# side_wide.net
KiCad netlist of a schematic drawn in EAGLE
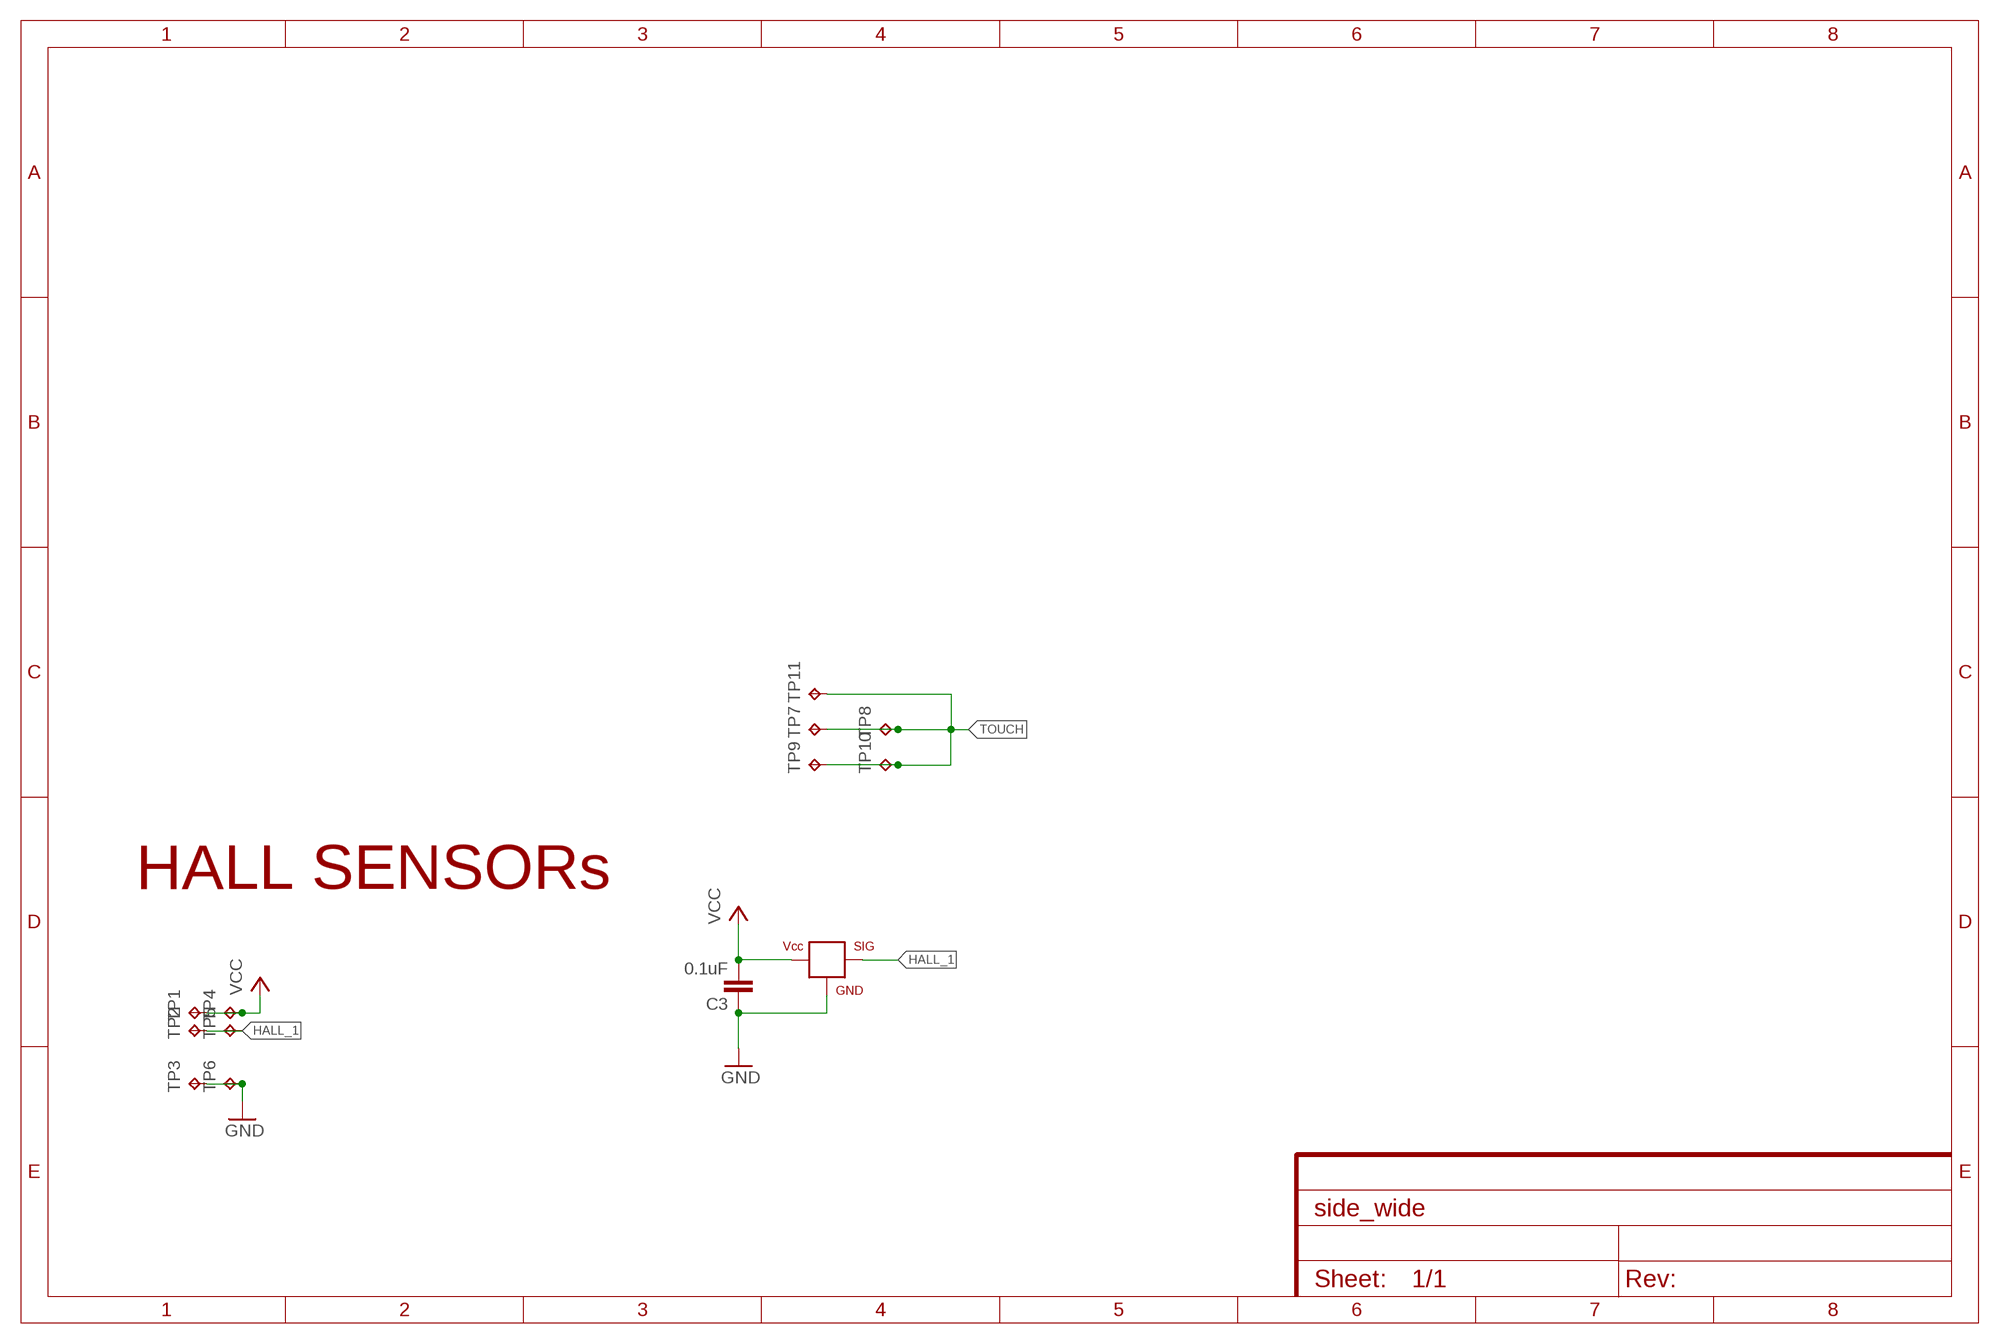
[diagram p0: schematic, sheet 1]

(export (version "E")
  (design (tool "Eeschema 10.0.6"))
  (components
    (comp (ref "C3")
      (value "0.1uF")
      (footprint "eagle-import:0603-CAP")
      (libsource (lib "eagle-import") (part "CAP0603-CAP"))
    )
    (comp (ref "HALL")
      (value "HALLEFFECT-A1326")
      (footprint "eagle-import:SOT23-3")
      (libsource (lib "eagle-import") (part "HALLEFFECT-A1326"))
    )
    (comp (ref "TP1")
      (value "TPTP10SQ")
      (footprint "eagle-import:TP10SQ")
      (libsource (lib "eagle-import") (part "TPTP10SQ"))
    )
    (comp (ref "TP2")
      (value "TPTP10SQ")
      (footprint "eagle-import:TP10SQ")
      (libsource (lib "eagle-import") (part "TPTP10SQ"))
    )
    (comp (ref "TP3")
      (value "TPTP10SQ")
      (footprint "eagle-import:TP10SQ")
      (libsource (lib "eagle-import") (part "TPTP10SQ"))
    )
    (comp (ref "TP4")
      (value "TPTP10SQ")
      (footprint "eagle-import:TP10SQ")
      (libsource (lib "eagle-import") (part "TPTP10SQ"))
    )
    (comp (ref "TP5")
      (value "TPTP10SQ")
      (footprint "eagle-import:TP10SQ")
      (libsource (lib "eagle-import") (part "TPTP10SQ"))
    )
    (comp (ref "TP6")
      (value "TPTP10SQ")
      (footprint "eagle-import:TP10SQ")
      (libsource (lib "eagle-import") (part "TPTP10SQ"))
    )
    (comp (ref "TP7")
      (value "TPTP10SQ")
      (footprint "eagle-import:TP10SQ")
      (libsource (lib "eagle-import") (part "TPTP10SQ"))
    )
    (comp (ref "TP8")
      (value "TPTP10SQ")
      (footprint "eagle-import:TP10SQ")
      (libsource (lib "eagle-import") (part "TPTP10SQ"))
    )
    (comp (ref "TP9")
      (value "TPTP10SQ")
      (footprint "eagle-import:TP10SQ")
      (libsource (lib "eagle-import") (part "TPTP10SQ"))
    )
    (comp (ref "TP10")
      (value "TPTP10SQ")
      (footprint "eagle-import:TP10SQ")
      (libsource (lib "eagle-import") (part "TPTP10SQ"))
    )
    (comp (ref "TP11")
      (value "TPTP10SQ")
      (footprint "eagle-import:TP10SQ")
      (libsource (lib "eagle-import") (part "TPTP10SQ"))
    )
  )
  (nets
    (net (code "1") (name "GND") (class "Default")
      (node (ref "C3") (pin "1") (pinfunction "1_1") (pintype "passive"))
      (node (ref "HALL") (pin "3") (pinfunction "GND_3") (pintype "bidirectional"))
      (node (ref "TP3") (pin "TP") (pinfunction "TP_TP") (pintype "input"))
      (node (ref "TP6") (pin "TP") (pinfunction "TP_TP") (pintype "input"))
    )
    (net (code "2") (name "HALL_1") (class "Default")
      (node (ref "HALL") (pin "2") (pinfunction "SIG_2") (pintype "bidirectional"))
      (node (ref "TP2") (pin "TP") (pinfunction "TP_TP") (pintype "input"))
      (node (ref "TP5") (pin "TP") (pinfunction "TP_TP") (pintype "input"))
    )
    (net (code "3") (name "TOUCH") (class "Default")
      (node (ref "TP10") (pin "TP") (pinfunction "TP_TP") (pintype "input"))
      (node (ref "TP11") (pin "TP") (pinfunction "TP_TP") (pintype "input"))
      (node (ref "TP7") (pin "TP") (pinfunction "TP_TP") (pintype "input"))
      (node (ref "TP8") (pin "TP") (pinfunction "TP_TP") (pintype "input"))
      (node (ref "TP9") (pin "TP") (pinfunction "TP_TP") (pintype "input"))
    )
    (net (code "4") (name "VCC") (class "Default")
      (node (ref "C3") (pin "2") (pinfunction "2_2") (pintype "passive"))
      (node (ref "HALL") (pin "1") (pinfunction "VCC_1") (pintype "bidirectional"))
      (node (ref "TP1") (pin "TP") (pinfunction "TP_TP") (pintype "input"))
      (node (ref "TP4") (pin "TP") (pinfunction "TP_TP") (pintype "input"))
    )
  )
)
